# M_2_Adapter.net
KiCad netlist of a schematic drawn in Altium Designer
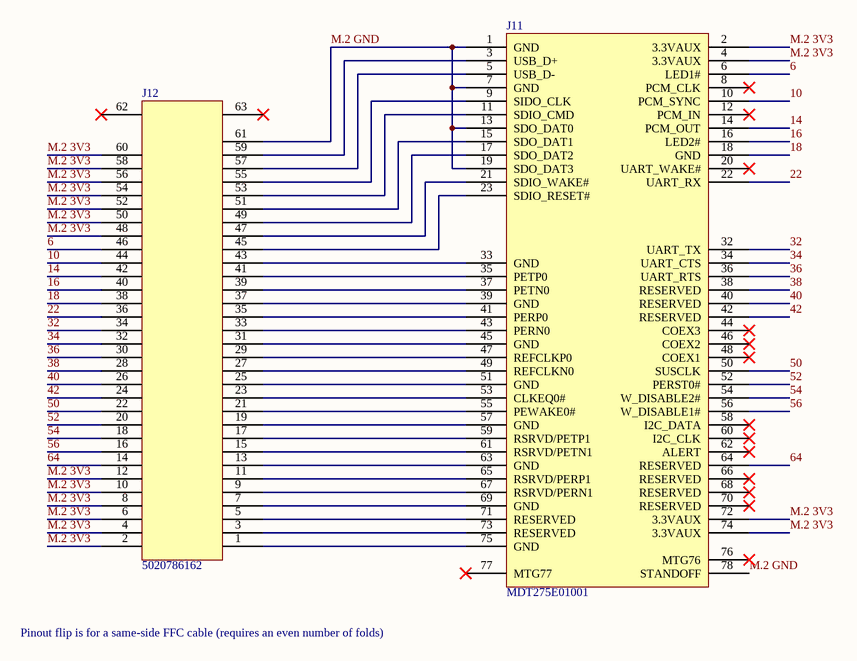
[diagram p0: M.2 Adapter.SchDoc]

(export (version "E")
  (design (tool "Eeschema 10.0.6"))
  (components
    (comp (ref "J11")
      (value "MDT275E01001")
      (footprint "MDT275E01001")
      (description "CONN M.2 E FMALE 67POS 0.020 GOLD")
      (libsource (lib "KBuchka-IntLib") (part "MDT275E01001"))
    )
    (comp (ref "J12")
      (value "5020786162")
      (footprint "5020786162")
      (description "Conn FPC Connector SKT 61 POS 0.25mm Solder RA SMD T/R")
      (libsource (lib "KBuchka-IntLib") (part "5020786162"))
    )
  )
  (nets
    (net (code "1") (name "/6") (class "Default")
      (node (ref "J11") (pin "6") (pinfunction "LED1#_6") (pintype "passive"))
      (node (ref "J12") (pin "46") (pintype "passive"))
    )
    (net (code "2") (name "/10") (class "Default")
      (node (ref "J11") (pin "10") (pinfunction "PCM_SYNC_10") (pintype "passive"))
      (node (ref "J12") (pin "44") (pintype "passive"))
    )
    (net (code "3") (name "/14") (class "Default")
      (node (ref "J11") (pin "14") (pinfunction "PCM_OUT_14") (pintype "passive"))
      (node (ref "J12") (pin "42") (pintype "passive"))
    )
    (net (code "4") (name "/16") (class "Default")
      (node (ref "J11") (pin "16") (pinfunction "LED2#_16") (pintype "passive"))
      (node (ref "J12") (pin "40") (pintype "passive"))
    )
    (net (code "5") (name "/18") (class "Default")
      (node (ref "J11") (pin "18") (pinfunction "GND_18") (pintype "passive"))
      (node (ref "J12") (pin "38") (pintype "passive"))
    )
    (net (code "6") (name "/22") (class "Default")
      (node (ref "J11") (pin "22") (pinfunction "UART_RX_22") (pintype "passive"))
      (node (ref "J12") (pin "36") (pintype "passive"))
    )
    (net (code "7") (name "/32") (class "Default")
      (node (ref "J11") (pin "32") (pinfunction "UART_TX_32") (pintype "passive"))
      (node (ref "J12") (pin "34") (pintype "passive"))
    )
    (net (code "8") (name "/34") (class "Default")
      (node (ref "J11") (pin "34") (pinfunction "UART_CTS_34") (pintype "passive"))
      (node (ref "J12") (pin "32") (pintype "passive"))
    )
    (net (code "9") (name "/36") (class "Default")
      (node (ref "J11") (pin "36") (pinfunction "UART_RTS_36") (pintype "passive"))
      (node (ref "J12") (pin "30") (pintype "passive"))
    )
    (net (code "10") (name "/38") (class "Default")
      (node (ref "J11") (pin "38") (pinfunction "RESERVED_38") (pintype "passive"))
      (node (ref "J12") (pin "28") (pintype "passive"))
    )
    (net (code "11") (name "/40") (class "Default")
      (node (ref "J11") (pin "40") (pinfunction "RESERVED_40") (pintype "passive"))
      (node (ref "J12") (pin "26") (pintype "passive"))
    )
    (net (code "12") (name "/42") (class "Default")
      (node (ref "J11") (pin "42") (pinfunction "RESERVED_42") (pintype "passive"))
      (node (ref "J12") (pin "24") (pintype "passive"))
    )
    (net (code "13") (name "/50") (class "Default")
      (node (ref "J11") (pin "50") (pinfunction "SUSCLK_50") (pintype "passive"))
      (node (ref "J12") (pin "22") (pintype "passive"))
    )
    (net (code "14") (name "/52") (class "Default")
      (node (ref "J11") (pin "52") (pinfunction "PERST0#_52") (pintype "passive"))
      (node (ref "J12") (pin "20") (pintype "passive"))
    )
    (net (code "15") (name "/54") (class "Default")
      (node (ref "J11") (pin "54") (pinfunction "W_DISABLE2#_54") (pintype "passive"))
      (node (ref "J12") (pin "18") (pintype "passive"))
    )
    (net (code "16") (name "/56") (class "Default")
      (node (ref "J11") (pin "56") (pinfunction "W_DISABLE1#_56") (pintype "passive"))
      (node (ref "J12") (pin "16") (pintype "passive"))
    )
    (net (code "17") (name "/64") (class "Default")
      (node (ref "J11") (pin "64") (pinfunction "RESERVED_64") (pintype "passive"))
      (node (ref "J12") (pin "14") (pintype "passive"))
    )
    (net (code "18") (name "/M.2 3V3") (class "Default")
      (node (ref "J11") (pin "2") (pinfunction "3.3VAUX_2") (pintype "passive"))
      (node (ref "J11") (pin "4") (pinfunction "3.3VAUX_4") (pintype "passive"))
      (node (ref "J11") (pin "72") (pinfunction "3.3VAUX_72") (pintype "passive"))
      (node (ref "J11") (pin "74") (pinfunction "3.3VAUX_74") (pintype "passive"))
      (node (ref "J12") (pin "10") (pintype "passive"))
      (node (ref "J12") (pin "12") (pintype "passive"))
      (node (ref "J12") (pin "2") (pintype "passive"))
      (node (ref "J12") (pin "4") (pintype "passive"))
      (node (ref "J12") (pin "48") (pintype "passive"))
      (node (ref "J12") (pin "50") (pintype "passive"))
      (node (ref "J12") (pin "52") (pintype "passive"))
      (node (ref "J12") (pin "54") (pintype "passive"))
      (node (ref "J12") (pin "56") (pintype "passive"))
      (node (ref "J12") (pin "58") (pintype "passive"))
      (node (ref "J12") (pin "6") (pintype "passive"))
      (node (ref "J12") (pin "60") (pintype "passive"))
      (node (ref "J12") (pin "8") (pintype "passive"))
    )
    (net (code "19") (name "/M.2 GND") (class "Default")
      (node (ref "J11") (pin "1") (pinfunction "GND_1") (pintype "passive"))
      (node (ref "J11") (pin "13") (pinfunction "SDO_DAT0_13") (pintype "passive"))
      (node (ref "J11") (pin "19") (pinfunction "SDO_DAT3_19") (pintype "passive"))
      (node (ref "J11") (pin "7") (pinfunction "GND_7") (pintype "passive"))
      (node (ref "J11") (pin "78") (pinfunction "STANDOFF_78") (pintype "passive"))
      (node (ref "J12") (pin "61") (pintype "passive"))
    )
    (net (code "20") (name "Net-(J11-CLKEQ0#)") (class "Default")
      (node (ref "J11") (pin "53") (pinfunction "CLKEQ0#_53") (pintype "passive"))
      (node (ref "J12") (pin "23") (pintype "passive"))
    )
    (net (code "21") (name "Net-(J11-GND-Pad33)") (class "Default")
      (node (ref "J11") (pin "33") (pinfunction "GND_33") (pintype "passive"))
      (node (ref "J12") (pin "43") (pintype "passive"))
    )
    (net (code "22") (name "Net-(J11-GND-Pad39)") (class "Default")
      (node (ref "J11") (pin "39") (pinfunction "GND_39") (pintype "passive"))
      (node (ref "J12") (pin "37") (pintype "passive"))
    )
    (net (code "23") (name "Net-(J11-GND-Pad45)") (class "Default")
      (node (ref "J11") (pin "45") (pinfunction "GND_45") (pintype "passive"))
      (node (ref "J12") (pin "31") (pintype "passive"))
    )
    (net (code "24") (name "Net-(J11-GND-Pad51)") (class "Default")
      (node (ref "J11") (pin "51") (pinfunction "GND_51") (pintype "passive"))
      (node (ref "J12") (pin "25") (pintype "passive"))
    )
    (net (code "25") (name "Net-(J11-GND-Pad57)") (class "Default")
      (node (ref "J11") (pin "57") (pinfunction "GND_57") (pintype "passive"))
      (node (ref "J12") (pin "19") (pintype "passive"))
    )
    (net (code "26") (name "Net-(J11-GND-Pad63)") (class "Default")
      (node (ref "J11") (pin "63") (pinfunction "GND_63") (pintype "passive"))
      (node (ref "J12") (pin "13") (pintype "passive"))
    )
    (net (code "27") (name "Net-(J11-GND-Pad69)") (class "Default")
      (node (ref "J11") (pin "69") (pinfunction "GND_69") (pintype "passive"))
      (node (ref "J12") (pin "7") (pintype "passive"))
    )
    (net (code "28") (name "Net-(J11-GND-Pad75)") (class "Default")
      (node (ref "J11") (pin "75") (pinfunction "GND_75") (pintype "passive"))
      (node (ref "J12") (pin "1") (pintype "passive"))
    )
    (net (code "29") (name "Net-(J11-PERN0)") (class "Default")
      (node (ref "J11") (pin "43") (pinfunction "PERN0_43") (pintype "passive"))
      (node (ref "J12") (pin "33") (pintype "passive"))
    )
    (net (code "30") (name "Net-(J11-PERP0)") (class "Default")
      (node (ref "J11") (pin "41") (pinfunction "PERP0_41") (pintype "passive"))
      (node (ref "J12") (pin "35") (pintype "passive"))
    )
    (net (code "31") (name "Net-(J11-PETN0)") (class "Default")
      (node (ref "J11") (pin "37") (pinfunction "PETN0_37") (pintype "passive"))
      (node (ref "J12") (pin "39") (pintype "passive"))
    )
    (net (code "32") (name "Net-(J11-PETP0)") (class "Default")
      (node (ref "J11") (pin "35") (pinfunction "PETP0_35") (pintype "passive"))
      (node (ref "J12") (pin "41") (pintype "passive"))
    )
    (net (code "33") (name "Net-(J11-PEWAKE0#)") (class "Default")
      (node (ref "J11") (pin "55") (pinfunction "PEWAKE0#_55") (pintype "passive"))
      (node (ref "J12") (pin "21") (pintype "passive"))
    )
    (net (code "34") (name "Net-(J11-REFCLKN0)") (class "Default")
      (node (ref "J11") (pin "49") (pinfunction "REFCLKN0_49") (pintype "passive"))
      (node (ref "J12") (pin "27") (pintype "passive"))
    )
    (net (code "35") (name "Net-(J11-REFCLKP0)") (class "Default")
      (node (ref "J11") (pin "47") (pinfunction "REFCLKP0_47") (pintype "passive"))
      (node (ref "J12") (pin "29") (pintype "passive"))
    )
    (net (code "36") (name "Net-(J11-RESERVED-Pad71)") (class "Default")
      (node (ref "J11") (pin "71") (pinfunction "RESERVED_71") (pintype "passive"))
      (node (ref "J12") (pin "5") (pintype "passive"))
    )
    (net (code "37") (name "Net-(J11-RESERVED-Pad73)") (class "Default")
      (node (ref "J11") (pin "73") (pinfunction "RESERVED_73") (pintype "passive"))
      (node (ref "J12") (pin "3") (pintype "passive"))
    )
    (net (code "38") (name "Net-(J11-RSRVD{slash}PERN1)") (class "Default")
      (node (ref "J11") (pin "67") (pinfunction "RSRVD/PERN1_67") (pintype "passive"))
      (node (ref "J12") (pin "9") (pintype "passive"))
    )
    (net (code "39") (name "Net-(J11-RSRVD{slash}PERP1)") (class "Default")
      (node (ref "J11") (pin "65") (pinfunction "RSRVD/PERP1_65") (pintype "passive"))
      (node (ref "J12") (pin "11") (pintype "passive"))
    )
    (net (code "40") (name "Net-(J11-RSRVD{slash}PETN1)") (class "Default")
      (node (ref "J11") (pin "61") (pinfunction "RSRVD/PETN1_61") (pintype "passive"))
      (node (ref "J12") (pin "15") (pintype "passive"))
    )
    (net (code "41") (name "Net-(J11-RSRVD{slash}PETP1)") (class "Default")
      (node (ref "J11") (pin "59") (pinfunction "RSRVD/PETP1_59") (pintype "passive"))
      (node (ref "J12") (pin "17") (pintype "passive"))
    )
    (net (code "42") (name "Net-(J11-SDIO_CMD)") (class "Default")
      (node (ref "J11") (pin "11") (pinfunction "SDIO_CMD_11") (pintype "passive"))
      (node (ref "J12") (pin "53") (pintype "passive"))
    )
    (net (code "43") (name "Net-(J11-SDIO_RESET#)") (class "Default")
      (node (ref "J11") (pin "23") (pinfunction "SDIO_RESET#_23") (pintype "passive"))
      (node (ref "J12") (pin "45") (pintype "passive"))
    )
    (net (code "44") (name "Net-(J11-SDIO_WAKE#)") (class "Default")
      (node (ref "J11") (pin "21") (pinfunction "SDIO_WAKE#_21") (pintype "passive"))
      (node (ref "J12") (pin "47") (pintype "passive"))
    )
    (net (code "45") (name "Net-(J11-SDO_DAT1)") (class "Default")
      (node (ref "J11") (pin "15") (pinfunction "SDO_DAT1_15") (pintype "passive"))
      (node (ref "J12") (pin "51") (pintype "passive"))
    )
    (net (code "46") (name "Net-(J11-SDO_DAT2)") (class "Default")
      (node (ref "J11") (pin "17") (pinfunction "SDO_DAT2_17") (pintype "passive"))
      (node (ref "J12") (pin "49") (pintype "passive"))
    )
    (net (code "47") (name "Net-(J11-SIDO_CLK)") (class "Default")
      (node (ref "J11") (pin "9") (pinfunction "SIDO_CLK_9") (pintype "passive"))
      (node (ref "J12") (pin "55") (pintype "passive"))
    )
    (net (code "48") (name "Net-(J11-USB_D+)") (class "Default")
      (node (ref "J11") (pin "3") (pinfunction "USB_D+_3") (pintype "passive"))
      (node (ref "J12") (pin "59") (pintype "passive"))
    )
    (net (code "49") (name "Net-(J11-USB_D-)") (class "Default")
      (node (ref "J11") (pin "5") (pinfunction "USB_D-_5") (pintype "passive"))
      (node (ref "J12") (pin "57") (pintype "passive"))
    )
    (net (code "50") (name "unconnected-(J11-ALERT-Pad62)") (class "Default")
      (node (ref "J11") (pin "62") (pinfunction "ALERT_62") (pintype "passive+no_connect"))
    )
    (net (code "51") (name "unconnected-(J11-COEX1-Pad48)") (class "Default")
      (node (ref "J11") (pin "48") (pinfunction "COEX1_48") (pintype "passive+no_connect"))
    )
    (net (code "52") (name "unconnected-(J11-COEX2-Pad46)") (class "Default")
      (node (ref "J11") (pin "46") (pinfunction "COEX2_46") (pintype "passive+no_connect"))
    )
    (net (code "53") (name "unconnected-(J11-COEX3-Pad44)") (class "Default")
      (node (ref "J11") (pin "44") (pinfunction "COEX3_44") (pintype "passive+no_connect"))
    )
    (net (code "54") (name "unconnected-(J11-I2C_CLK-Pad60)") (class "Default")
      (node (ref "J11") (pin "60") (pinfunction "I2C_CLK_60") (pintype "passive+no_connect"))
    )
    (net (code "55") (name "unconnected-(J11-I2C_DATA-Pad58)") (class "Default")
      (node (ref "J11") (pin "58") (pinfunction "I2C_DATA_58") (pintype "passive+no_connect"))
    )
    (net (code "56") (name "unconnected-(J11-MTG76-Pad76)") (class "Default")
      (node (ref "J11") (pin "76") (pinfunction "MTG76_76") (pintype "passive+no_connect"))
    )
    (net (code "57") (name "unconnected-(J11-MTG77-Pad77)") (class "Default")
      (node (ref "J11") (pin "77") (pinfunction "MTG77_77") (pintype "passive+no_connect"))
    )
    (net (code "58") (name "unconnected-(J11-PCM_CLK-Pad8)") (class "Default")
      (node (ref "J11") (pin "8") (pinfunction "PCM_CLK_8") (pintype "passive+no_connect"))
    )
    (net (code "59") (name "unconnected-(J11-PCM_IN-Pad12)") (class "Default")
      (node (ref "J11") (pin "12") (pinfunction "PCM_IN_12") (pintype "passive+no_connect"))
    )
    (net (code "60") (name "unconnected-(J11-RESERVED-Pad66)") (class "Default")
      (node (ref "J11") (pin "66") (pinfunction "RESERVED_66") (pintype "passive+no_connect"))
    )
    (net (code "61") (name "unconnected-(J11-RESERVED-Pad68)") (class "Default")
      (node (ref "J11") (pin "68") (pinfunction "RESERVED_68") (pintype "passive+no_connect"))
    )
    (net (code "62") (name "unconnected-(J11-RESERVED-Pad70)") (class "Default")
      (node (ref "J11") (pin "70") (pinfunction "RESERVED_70") (pintype "passive+no_connect"))
    )
    (net (code "63") (name "unconnected-(J11-UART_WAKE#-Pad20)") (class "Default")
      (node (ref "J11") (pin "20") (pinfunction "UART_WAKE#_20") (pintype "passive+no_connect"))
    )
    (net (code "64") (name "unconnected-(J12-Pad62)") (class "Default")
      (node (ref "J12") (pin "62") (pintype "passive+no_connect"))
    )
    (net (code "65") (name "unconnected-(J12-Pad63)") (class "Default")
      (node (ref "J12") (pin "63") (pintype "passive+no_connect"))
    )
  )
)
